# Power_and_Connectors.net
KiCad netlist of a schematic drawn in Altium Designer
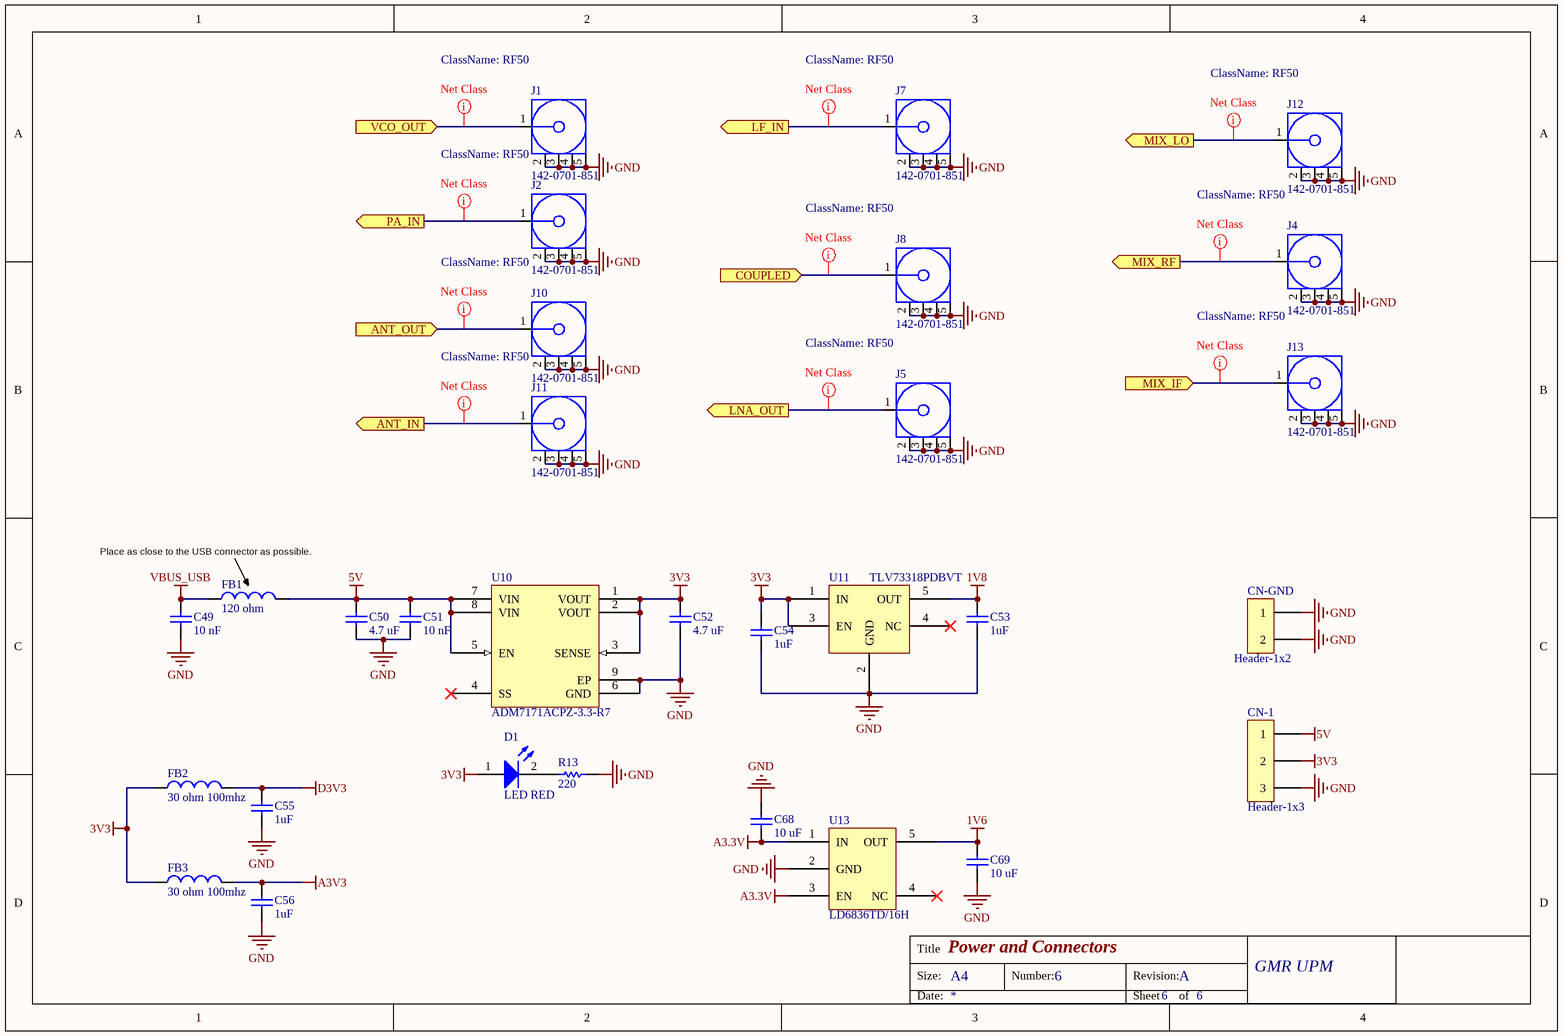
[diagram p0: Power and Connectors.SchDoc]

(export (version "E")
  (design (tool "Eeschema 10.0.6"))
  (components
    (comp (ref "C49")
      (value "10 nF")
      (footprint "Chip2PinSM127P600-8N_CAP0402")
      (description "CAP CER 10000PF 25V X7R 0402")
      (fields
        (field (name "MANUFACTURER") "Samsung Electro-Mechanics America, Inc.")
        (field (name "MANUFACTURER PART NUMBER") "CL05B103KA5NNNC")
      )
      (libsource (lib "Components") (part "CL05B103KA5NNNC"))
    )
    (comp (ref "C50")
      (value "4.7 uF")
      (footprint "CAPC1608X10L")
      (description "Multilayer Ceramic Capacitors MLCC - SMD/SMT 0603 4.7uF 16volts X5R + - 10%")
      (fields
        (field (name "MANUFACTURER") "Murata Electronics")
        (field (name "MANUFACTURER PART NUMBER") "GRM188R61C475KAAJD")
      )
      (libsource (lib "Components") (part "GRM188R61C475KAAJD"))
    )
    (comp (ref "C51")
      (value "10 nF")
      (footprint "Chip2PinSM127P600-8N_CAP0402")
      (description "CAP CER 10000PF 25V X7R 0402")
      (fields
        (field (name "MANUFACTURER") "Samsung Electro-Mechanics America, Inc.")
        (field (name "MANUFACTURER PART NUMBER") "CL05B103KA5NNNC")
      )
      (libsource (lib "Components") (part "CL05B103KA5NNNC"))
    )
    (comp (ref "C52")
      (value "4.7 uF")
      (footprint "CAPC1608X10L")
      (description "Multilayer Ceramic Capacitors MLCC - SMD/SMT 0603 4.7uF 16volts X5R + - 10%")
      (fields
        (field (name "MANUFACTURER") "Murata Electronics")
        (field (name "MANUFACTURER PART NUMBER") "GRM188R61C475KAAJD")
      )
      (libsource (lib "Components") (part "GRM188R61C475KAAJD"))
    )
    (comp (ref "C53")
      (value "1uF")
      (footprint "0603 Cap")
      (description "CAP CER 1UF 16V X7R 0603")
      (fields
        (field (name "MANUFACTURER") "Samsung Electro-Mechanics America, Inc.")
        (field (name "MANUFACTURER PART NUMBER") "CL10B105MO8NNWC")
      )
      (libsource (lib "Componentes_base") (part "CL10B105MO8NNWC"))
    )
    (comp (ref "C54")
      (value "1uF")
      (footprint "0603 Cap")
      (description "CAP CER 1UF 16V X7R 0603")
      (fields
        (field (name "MANUFACTURER") "Samsung Electro-Mechanics America, Inc.")
        (field (name "MANUFACTURER PART NUMBER") "CL10B105MO8NNWC")
      )
      (libsource (lib "Componentes_base") (part "CL10B105MO8NNWC"))
    )
    (comp (ref "C55")
      (value "1uF")
      (footprint "0603 Cap")
      (description "CAP CER 1UF 16V X7R 0603")
      (fields
        (field (name "MANUFACTURER") "Samsung Electro-Mechanics America, Inc.")
        (field (name "MANUFACTURER PART NUMBER") "CL10B105MO8NNWC")
      )
      (libsource (lib "componentes") (part "CL10B105MO8NNWC"))
    )
    (comp (ref "C56")
      (value "1uF")
      (footprint "0603 Cap")
      (description "CAP CER 1UF 16V X7R 0603")
      (fields
        (field (name "MANUFACTURER") "Samsung Electro-Mechanics America, Inc.")
        (field (name "MANUFACTURER PART NUMBER") "CL10B105MO8NNWC")
      )
      (libsource (lib "componentes") (part "CL10B105MO8NNWC"))
    )
    (comp (ref "C68")
      (value "10 uF")
      (footprint "CAPC1608X10L")
      (description "CAP CER 10UF 16V 20% X5R 0603")
      (fields
        (field (name "MANUFACTURER") "Murata Electronics North America")
        (field (name "MANUFACTURER PART NUMBER") "GRM188R61C106MA73D")
      )
      (libsource (lib "Componentes_base") (part "GRM188R61C106MA73D"))
    )
    (comp (ref "C69")
      (value "10 uF")
      (footprint "CAPC1608X10L")
      (description "CAP CER 10UF 16V 20% X5R 0603")
      (fields
        (field (name "MANUFACTURER") "Murata Electronics North America")
        (field (name "MANUFACTURER PART NUMBER") "GRM188R61C106MA73D")
      )
      (libsource (lib "Componentes_base") (part "GRM188R61C106MA73D"))
    )
    (comp (ref "CN-1")
      (value "Header-1x3")
      (footprint "Header-1x3-Jumper")
      (libsource (lib "B105lib") (part "Header-1x3"))
    )
    (comp (ref "CN-GND")
      (value "Header-1x2")
      (footprint "HEADER-1x2-Jumper")
      (libsource (lib "B105lib") (part "Header-1x2"))
    )
    (comp (ref "D1")
      (value "LED RED")
      (footprint "0603 LED")
      (description "LED RED CLEAR 0603 SMD")
      (fields
        (field (name "MANUFACTURER") "Lite-On Inc.")
        (field (name "MANUFACTURER PART NUMBER") "LTST-C191KRKT")
      )
      (libsource (lib "Componentes_base") (part "LTST-C191KRKT"))
    )
    (comp (ref "FB1")
      (value "120 ohm")
      (footprint "INDC1608X08L")
      (description "FERRITE BEAD 120 OHM 0603 1LN")
      (fields
        (field (name "MANUFACTURER") "Murata Electronics North America")
        (field (name "MANUFACTURER PART NUMBER") "BLM18PG121SN1D")
      )
      (libsource (lib "Componentes_base") (part "BLM18PG121SN1D"))
    )
    (comp (ref "FB2")
      (value "30 ohm 100mhz")
      (footprint "0805 Ind")
      (description "FERRITE BEAD 30 OHM 0805 1LN")
      (fields
        (field (name "MANUFACTURER") "Bourns Inc.")
        (field (name "MANUFACTURER PART NUMBER") "MH2029-300Y")
      )
      (libsource (lib "Componentes_base") (part "MH2029-300Y"))
    )
    (comp (ref "FB3")
      (value "30 ohm 100mhz")
      (footprint "0805 Ind")
      (description "FERRITE BEAD 30 OHM 0805 1LN")
      (fields
        (field (name "MANUFACTURER") "Bourns Inc.")
        (field (name "MANUFACTURER PART NUMBER") "MH2029-300Y")
      )
      (libsource (lib "componentes") (part "MH2029-300Y"))
    )
    (comp (ref "J1")
      (value "142-0701-851")
      (footprint "142-0701-851")
      (description "RF Connectors / Coaxial Connectors PC END MT JCK GLD .062 BOARDS TAB")
      (fields (field (name "MANUFACTURER") "Johnson / Cinch Connectivity Solutions"))
      (libsource (lib "Componentes_base") (part "142-0701-851"))
    )
    (comp (ref "J2")
      (value "142-0701-851")
      (footprint "142-0701-851")
      (description "RF Connectors / Coaxial Connectors PC END MT JCK GLD .062 BOARDS TAB")
      (fields (field (name "MANUFACTURER") "Johnson / Cinch Connectivity Solutions"))
      (libsource (lib "Componentes_base") (part "142-0701-851"))
    )
    (comp (ref "J4")
      (value "142-0701-851")
      (footprint "142-0701-851")
      (description "RF Connectors / Coaxial Connectors PC END MT JCK GLD .062 BOARDS TAB")
      (fields (field (name "MANUFACTURER") "Johnson / Cinch Connectivity Solutions"))
      (libsource (lib "Componentes_base") (part "142-0701-851"))
    )
    (comp (ref "J5")
      (value "142-0701-851")
      (footprint "142-0701-851")
      (description "RF Connectors / Coaxial Connectors PC END MT JCK GLD .062 BOARDS TAB")
      (fields (field (name "MANUFACTURER") "Johnson / Cinch Connectivity Solutions"))
      (libsource (lib "Componentes_base") (part "142-0701-851"))
    )
    (comp (ref "J7")
      (value "142-0701-851")
      (footprint "142-0701-851")
      (description "RF Connectors / Coaxial Connectors PC END MT JCK GLD .062 BOARDS TAB")
      (fields (field (name "MANUFACTURER") "Johnson / Cinch Connectivity Solutions"))
      (libsource (lib "Componentes_base") (part "142-0701-851"))
    )
    (comp (ref "J8")
      (value "142-0701-851")
      (footprint "142-0701-851")
      (description "RF Connectors / Coaxial Connectors PC END MT JCK GLD .062 BOARDS TAB")
      (fields (field (name "MANUFACTURER") "Johnson / Cinch Connectivity Solutions"))
      (libsource (lib "Componentes_base") (part "142-0701-851"))
    )
    (comp (ref "J10")
      (value "142-0701-851")
      (footprint "142-0701-851")
      (description "RF Connectors / Coaxial Connectors PC END MT JCK GLD .062 BOARDS TAB")
      (fields (field (name "MANUFACTURER") "Johnson / Cinch Connectivity Solutions"))
      (libsource (lib "Componentes_base") (part "142-0701-851"))
    )
    (comp (ref "J11")
      (value "142-0701-851")
      (footprint "142-0701-851")
      (description "RF Connectors / Coaxial Connectors PC END MT JCK GLD .062 BOARDS TAB")
      (fields (field (name "MANUFACTURER") "Johnson / Cinch Connectivity Solutions"))
      (libsource (lib "Componentes_base") (part "142-0701-851"))
    )
    (comp (ref "J12")
      (value "142-0701-851")
      (footprint "142-0701-851")
      (description "RF Connectors / Coaxial Connectors PC END MT JCK GLD .062 BOARDS TAB")
      (fields (field (name "MANUFACTURER") "Johnson / Cinch Connectivity Solutions"))
      (libsource (lib "Componentes_base") (part "142-0701-851"))
    )
    (comp (ref "J13")
      (value "142-0701-851")
      (footprint "142-0701-851")
      (description "RF Connectors / Coaxial Connectors PC END MT JCK GLD .062 BOARDS TAB")
      (fields (field (name "MANUFACTURER") "Johnson / Cinch Connectivity Solutions"))
      (libsource (lib "Componentes_base") (part "142-0701-851"))
    )
    (comp (ref "R13")
      (value "220")
      (footprint "0603 Res")
      (description "RES SMD 220 OHM 1% 1/10W 0603")
      (fields
        (field (name "MANUFACTURER") "Yageo")
        (field (name "MANUFACTURER PART NUMBER") "RC0603FR-07220RL")
      )
      (libsource (lib "Componentes_base") (part "RC0603FR-07220RL"))
    )
    (comp (ref "U10")
      (value "ADM7171ACPZ-3.3-R7")
      (footprint "SON50P300X80_HS-9N LFCSP_WD Analog")
      (description "IC REG LDO 3.3V 1A 8-LFCSP")
      (fields (field (name "MANUFACTURER") "Analog Devices Inc."))
      (libsource (lib "Components") (part "ADM7171ACPZ-3.3-R7"))
    )
    (comp (ref "U11")
      (value "TLV73318PDBVT")
      (footprint "SOT95P280X145-5N")
      (description "IC REG LINEAR 1.8V 300MA SOT23-5")
      (fields (field (name "MANUFACTURER") "Texas Instruments"))
      (libsource (lib "Componentes_base") (part "TLV73318PDBVT"))
    )
    (comp (ref "U13")
      (value "LD6836TD/16H")
      (footprint "SOT-753")
      (description "NEXPERIA - LD6836TD/16H - LDO, 5,5V, 0.09VDO, 0,3A, 1,6V, 5SOT753")
      (fields (field (name "MANUFACTURER") "NEXPERIA"))
      (libsource (lib "Componentes_base") (part "LD6836TD/16H"))
    )
  )
  (nets
    (net (code "1") (name "/ANT_IN") (class "Default")
      (node (ref "J11") (pin "1") (pinfunction "Signal_1") (pintype "bidirectional"))
    )
    (net (code "2") (name "/ANT_OUT") (class "Default")
      (node (ref "J10") (pin "1") (pinfunction "Signal_1") (pintype "bidirectional"))
    )
    (net (code "3") (name "/COUPLED") (class "Default")
      (node (ref "J8") (pin "1") (pinfunction "Signal_1") (pintype "bidirectional"))
    )
    (net (code "4") (name "/LF_IN") (class "Default")
      (node (ref "J7") (pin "1") (pinfunction "Signal_1") (pintype "bidirectional"))
    )
    (net (code "5") (name "/LNA_OUT") (class "Default")
      (node (ref "J5") (pin "1") (pinfunction "Signal_1") (pintype "bidirectional"))
    )
    (net (code "6") (name "/MIX_IF") (class "Default")
      (node (ref "J13") (pin "1") (pinfunction "Signal_1") (pintype "bidirectional"))
    )
    (net (code "7") (name "/MIX_LO") (class "Default")
      (node (ref "J12") (pin "1") (pinfunction "Signal_1") (pintype "bidirectional"))
    )
    (net (code "8") (name "/MIX_RF") (class "Default")
      (node (ref "J4") (pin "1") (pinfunction "Signal_1") (pintype "bidirectional"))
    )
    (net (code "9") (name "/PA_IN") (class "Default")
      (node (ref "J2") (pin "1") (pinfunction "Signal_1") (pintype "bidirectional"))
    )
    (net (code "10") (name "/VCO_OUT") (class "Default")
      (node (ref "J1") (pin "1") (pinfunction "Signal_1") (pintype "bidirectional"))
    )
    (net (code "11") (name "1V6") (class "Default")
      (node (ref "C69") (pin "2") (pinfunction "2_2") (pintype "passive"))
      (node (ref "U13") (pin "5") (pinfunction "OUT_5") (pintype "passive"))
    )
    (net (code "12") (name "1V8") (class "Default")
      (node (ref "C53") (pin "2") (pinfunction "2_2") (pintype "passive"))
      (node (ref "U11") (pin "5") (pinfunction "OUT_5") (pintype "passive"))
    )
    (net (code "13") (name "3V3") (class "Default")
      (node (ref "C52") (pin "2") (pinfunction "2_2") (pintype "passive"))
      (node (ref "C54") (pin "2") (pinfunction "2_2") (pintype "passive"))
      (node (ref "CN-1") (pin "2") (pinfunction "2_2") (pintype "passive"))
      (node (ref "D1") (pin "1") (pinfunction "A_1") (pintype "passive"))
      (node (ref "FB2") (pin "1") (pinfunction "1_1") (pintype "passive"))
      (node (ref "FB3") (pin "1") (pinfunction "1_1") (pintype "passive"))
      (node (ref "U10") (pin "1") (pinfunction "VOUT_1") (pintype "power_in"))
      (node (ref "U10") (pin "2") (pinfunction "VOUT_2") (pintype "power_in"))
      (node (ref "U10") (pin "3") (pinfunction "SENSE_3") (pintype "input"))
      (node (ref "U11") (pin "1") (pinfunction "IN_1") (pintype "passive"))
      (node (ref "U11") (pin "3") (pinfunction "EN_3") (pintype "passive"))
    )
    (net (code "14") (name "5V") (class "Default")
      (node (ref "C50") (pin "2") (pinfunction "2_2") (pintype "passive"))
      (node (ref "C51") (pin "2") (pinfunction "2_2") (pintype "passive"))
      (node (ref "CN-1") (pin "1") (pinfunction "1_1") (pintype "passive"))
      (node (ref "FB1") (pin "2") (pinfunction "2_2") (pintype "passive"))
      (node (ref "U10") (pin "5") (pinfunction "EN_5") (pintype "input"))
      (node (ref "U10") (pin "7") (pinfunction "VIN_7") (pintype "power_in"))
      (node (ref "U10") (pin "8") (pinfunction "VIN_8") (pintype "power_in"))
    )
    (net (code "15") (name "A3.3V") (class "Default")
      (node (ref "C68") (pin "1") (pinfunction "1_1") (pintype "passive"))
      (node (ref "U13") (pin "1") (pinfunction "IN_1") (pintype "passive"))
      (node (ref "U13") (pin "3") (pinfunction "EN_3") (pintype "passive"))
    )
    (net (code "16") (name "A3V3") (class "Default")
      (node (ref "C56") (pin "2") (pinfunction "2_2") (pintype "passive"))
      (node (ref "FB3") (pin "2") (pinfunction "2_2") (pintype "passive"))
    )
    (net (code "17") (name "D3V3") (class "Default")
      (node (ref "C55") (pin "2") (pinfunction "2_2") (pintype "passive"))
      (node (ref "FB2") (pin "2") (pinfunction "2_2") (pintype "passive"))
    )
    (net (code "18") (name "GND") (class "Default")
      (node (ref "C49") (pin "1") (pinfunction "1_1") (pintype "passive"))
      (node (ref "C50") (pin "1") (pinfunction "1_1") (pintype "passive"))
      (node (ref "C51") (pin "1") (pinfunction "1_1") (pintype "passive"))
      (node (ref "C52") (pin "1") (pinfunction "1_1") (pintype "passive"))
      (node (ref "C53") (pin "1") (pinfunction "1_1") (pintype "passive"))
      (node (ref "C54") (pin "1") (pinfunction "1_1") (pintype "passive"))
      (node (ref "C55") (pin "1") (pinfunction "1_1") (pintype "passive"))
      (node (ref "C56") (pin "1") (pinfunction "1_1") (pintype "passive"))
      (node (ref "C68") (pin "2") (pinfunction "2_2") (pintype "passive"))
      (node (ref "C69") (pin "1") (pinfunction "1_1") (pintype "passive"))
      (node (ref "CN-1") (pin "3") (pinfunction "3_3") (pintype "passive"))
      (node (ref "CN-GND") (pin "1") (pinfunction "1_1") (pintype "passive"))
      (node (ref "CN-GND") (pin "2") (pinfunction "2_2") (pintype "passive"))
      (node (ref "J1") (pin "2") (pinfunction "GND_2") (pintype "power_in"))
      (node (ref "J1") (pin "3") (pinfunction "GND_3") (pintype "power_in"))
      (node (ref "J1") (pin "4") (pinfunction "GND_4") (pintype "power_in"))
      (node (ref "J1") (pin "5") (pinfunction "GND_5") (pintype "power_in"))
      (node (ref "J10") (pin "2") (pinfunction "GND_2") (pintype "power_in"))
      (node (ref "J10") (pin "3") (pinfunction "GND_3") (pintype "power_in"))
      (node (ref "J10") (pin "4") (pinfunction "GND_4") (pintype "power_in"))
      (node (ref "J10") (pin "5") (pinfunction "GND_5") (pintype "power_in"))
      (node (ref "J11") (pin "2") (pinfunction "GND_2") (pintype "power_in"))
      (node (ref "J11") (pin "3") (pinfunction "GND_3") (pintype "power_in"))
      (node (ref "J11") (pin "4") (pinfunction "GND_4") (pintype "power_in"))
      (node (ref "J11") (pin "5") (pinfunction "GND_5") (pintype "power_in"))
      (node (ref "J12") (pin "2") (pinfunction "GND_2") (pintype "power_in"))
      (node (ref "J12") (pin "3") (pinfunction "GND_3") (pintype "power_in"))
      (node (ref "J12") (pin "4") (pinfunction "GND_4") (pintype "power_in"))
      (node (ref "J12") (pin "5") (pinfunction "GND_5") (pintype "power_in"))
      (node (ref "J13") (pin "2") (pinfunction "GND_2") (pintype "power_in"))
      (node (ref "J13") (pin "3") (pinfunction "GND_3") (pintype "power_in"))
      (node (ref "J13") (pin "4") (pinfunction "GND_4") (pintype "power_in"))
      (node (ref "J13") (pin "5") (pinfunction "GND_5") (pintype "power_in"))
      (node (ref "J2") (pin "2") (pinfunction "GND_2") (pintype "power_in"))
      (node (ref "J2") (pin "3") (pinfunction "GND_3") (pintype "power_in"))
      (node (ref "J2") (pin "4") (pinfunction "GND_4") (pintype "power_in"))
      (node (ref "J2") (pin "5") (pinfunction "GND_5") (pintype "power_in"))
      (node (ref "J4") (pin "2") (pinfunction "GND_2") (pintype "power_in"))
      (node (ref "J4") (pin "3") (pinfunction "GND_3") (pintype "power_in"))
      (node (ref "J4") (pin "4") (pinfunction "GND_4") (pintype "power_in"))
      (node (ref "J4") (pin "5") (pinfunction "GND_5") (pintype "power_in"))
      (node (ref "J5") (pin "2") (pinfunction "GND_2") (pintype "power_in"))
      (node (ref "J5") (pin "3") (pinfunction "GND_3") (pintype "power_in"))
      (node (ref "J5") (pin "4") (pinfunction "GND_4") (pintype "power_in"))
      (node (ref "J5") (pin "5") (pinfunction "GND_5") (pintype "power_in"))
      (node (ref "J7") (pin "2") (pinfunction "GND_2") (pintype "power_in"))
      (node (ref "J7") (pin "3") (pinfunction "GND_3") (pintype "power_in"))
      (node (ref "J7") (pin "4") (pinfunction "GND_4") (pintype "power_in"))
      (node (ref "J7") (pin "5") (pinfunction "GND_5") (pintype "power_in"))
      (node (ref "J8") (pin "2") (pinfunction "GND_2") (pintype "power_in"))
      (node (ref "J8") (pin "3") (pinfunction "GND_3") (pintype "power_in"))
      (node (ref "J8") (pin "4") (pinfunction "GND_4") (pintype "power_in"))
      (node (ref "J8") (pin "5") (pinfunction "GND_5") (pintype "power_in"))
      (node (ref "R13") (pin "2") (pinfunction "2_2") (pintype "passive"))
      (node (ref "U10") (pin "6") (pinfunction "GND_6") (pintype "power_in"))
      (node (ref "U10") (pin "9") (pinfunction "EP_9") (pintype "power_in"))
      (node (ref "U11") (pin "2") (pinfunction "GND_2") (pintype "passive"))
      (node (ref "U13") (pin "2") (pinfunction "GND_2") (pintype "passive"))
    )
    (net (code "19") (name "Net-(D1-C)") (class "Default")
      (node (ref "D1") (pin "2") (pinfunction "C_2") (pintype "passive"))
      (node (ref "R13") (pin "1") (pinfunction "1_1") (pintype "passive"))
    )
    (net (code "20") (name "VBUS_USB") (class "Default")
      (node (ref "C49") (pin "2") (pinfunction "2_2") (pintype "passive"))
      (node (ref "FB1") (pin "1") (pinfunction "1_1") (pintype "passive"))
    )
    (net (code "21") (name "unconnected-(U10-SS-Pad4)") (class "Default")
      (node (ref "U10") (pin "4") (pinfunction "SS_4") (pintype "passive+no_connect"))
    )
    (net (code "22") (name "unconnected-(U11-NC-Pad4)") (class "Default")
      (node (ref "U11") (pin "4") (pinfunction "NC_4") (pintype "passive+no_connect"))
    )
    (net (code "23") (name "unconnected-(U13-NC-Pad4)") (class "Default")
      (node (ref "U13") (pin "4") (pinfunction "NC_4") (pintype "passive+no_connect"))
    )
  )
)
